# Keypad.net
KiCad netlist of a schematic drawn in EAGLE
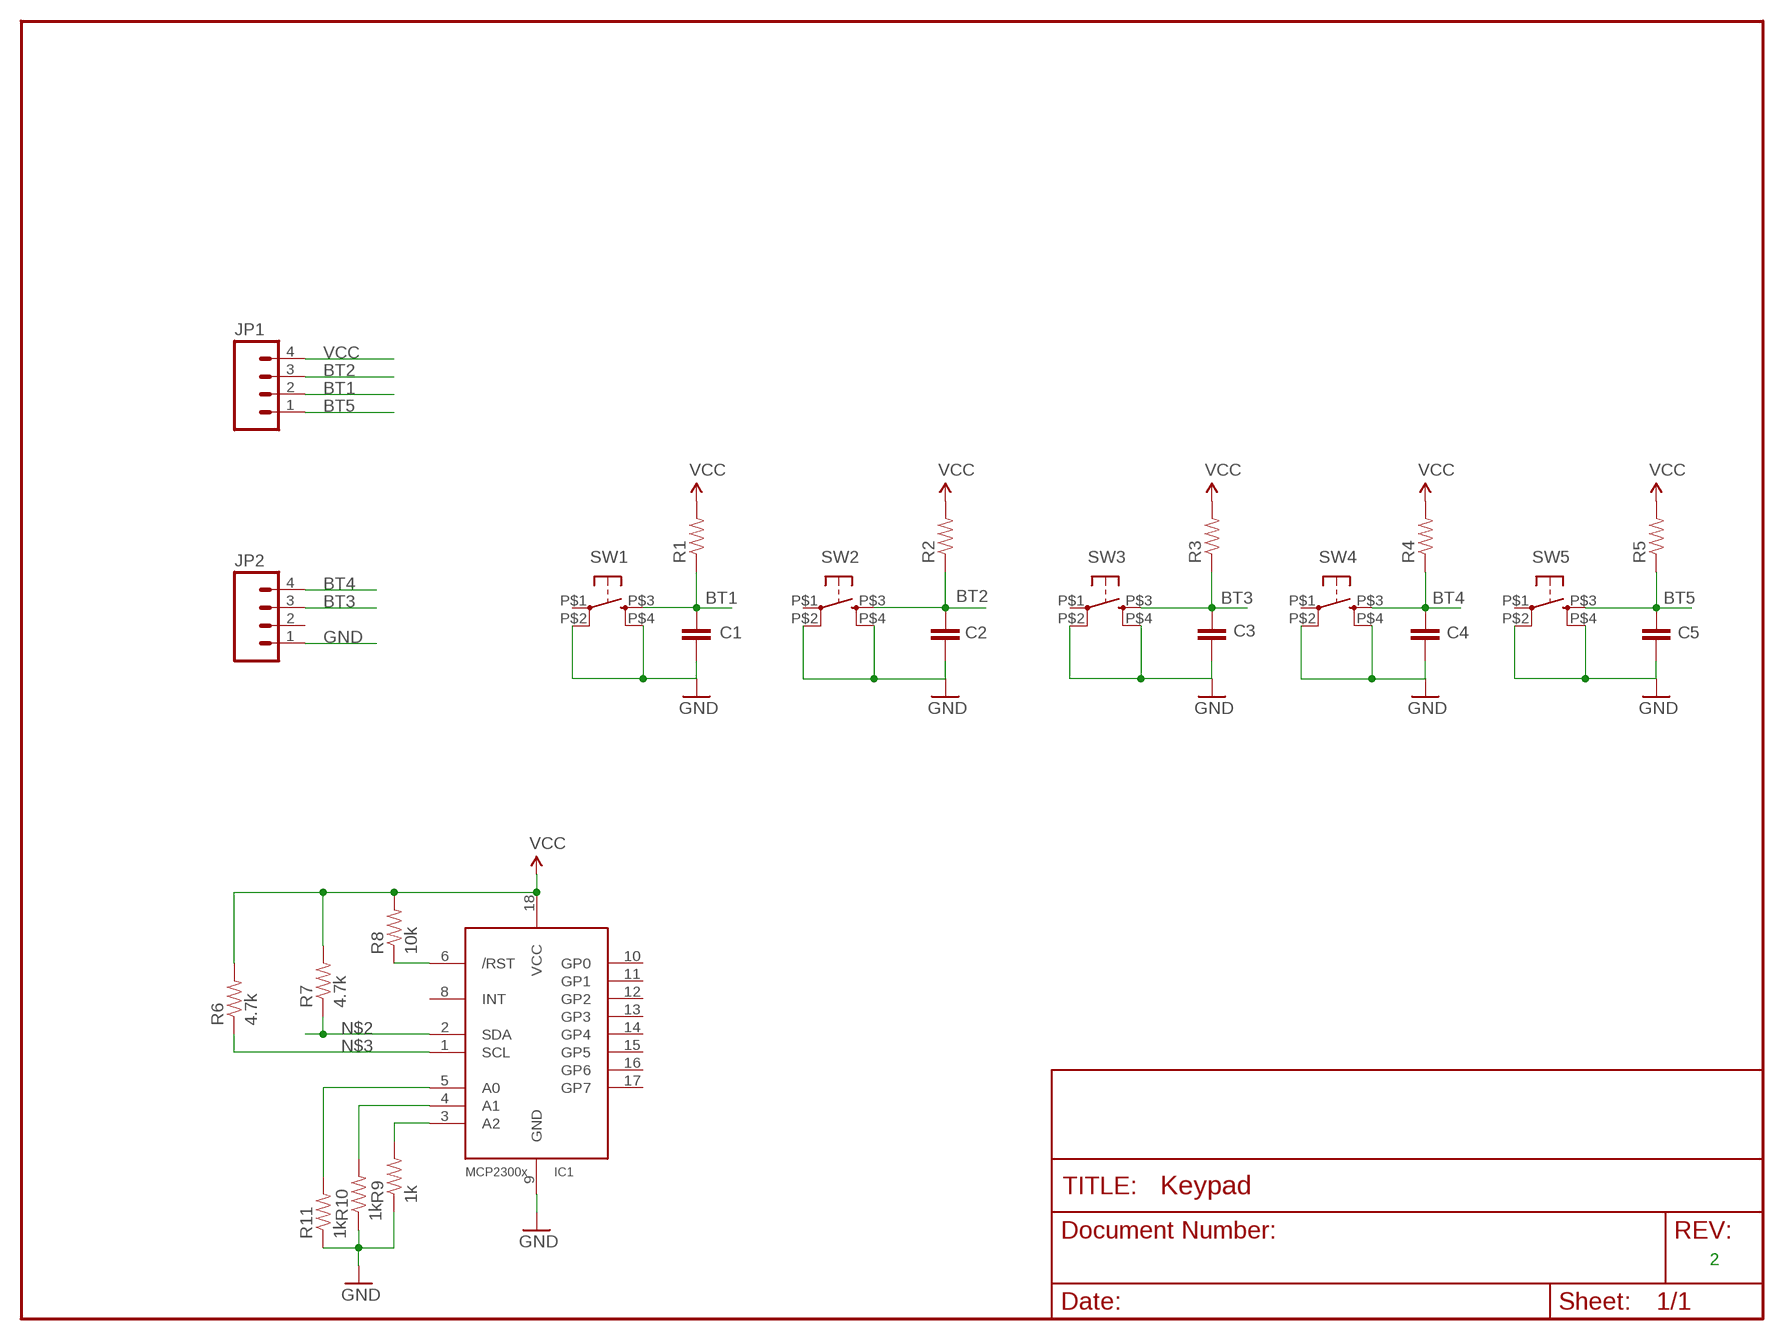
[diagram p0: schematic, sheet 1]

(export (version "E")
  (design (tool "Eeschema 10.0.6"))
  (components
    (comp (ref "C1")
      (value "CAP1206")
      (footprint "eagle-import:1206")
      (libsource (lib "eagle-import") (part "CAP1206"))
    )
    (comp (ref "C2")
      (value "CAP1206")
      (footprint "eagle-import:1206")
      (libsource (lib "eagle-import") (part "CAP1206"))
    )
    (comp (ref "C3")
      (value "CAP1206")
      (footprint "eagle-import:1206")
      (libsource (lib "eagle-import") (part "CAP1206"))
    )
    (comp (ref "C4")
      (value "CAP1206")
      (footprint "eagle-import:1206")
      (libsource (lib "eagle-import") (part "CAP1206"))
    )
    (comp (ref "C5")
      (value "CAP1206")
      (footprint "eagle-import:1206")
      (libsource (lib "eagle-import") (part "CAP1206"))
    )
    (comp (ref "IC1")
      (value "MCP2300X/SO")
      (footprint "eagle-import:SO18W")
      (libsource (lib "eagle-import") (part "MCP2300X/SO"))
    )
    (comp (ref "JP1")
      (value "M04LOCK")
      (footprint "eagle-import:1X04_LOCK")
      (libsource (lib "eagle-import") (part "M04LOCK"))
    )
    (comp (ref "JP2")
      (value "M04LOCK")
      (footprint "eagle-import:1X04_LOCK")
      (libsource (lib "eagle-import") (part "M04LOCK"))
    )
    (comp (ref "R1")
      (value "RESISTOR1206")
      (footprint "eagle-import:1206")
      (libsource (lib "eagle-import") (part "RESISTOR1206"))
    )
    (comp (ref "R2")
      (value "RESISTOR1206")
      (footprint "eagle-import:1206")
      (libsource (lib "eagle-import") (part "RESISTOR1206"))
    )
    (comp (ref "R3")
      (value "RESISTOR1206")
      (footprint "eagle-import:1206")
      (libsource (lib "eagle-import") (part "RESISTOR1206"))
    )
    (comp (ref "R4")
      (value "RESISTOR1206")
      (footprint "eagle-import:1206")
      (libsource (lib "eagle-import") (part "RESISTOR1206"))
    )
    (comp (ref "R5")
      (value "RESISTOR1206")
      (footprint "eagle-import:1206")
      (libsource (lib "eagle-import") (part "RESISTOR1206"))
    )
    (comp (ref "R6")
      (value "4.7k")
      (footprint "eagle-import:1206")
      (libsource (lib "eagle-import") (part "RESISTOR1206"))
    )
    (comp (ref "R7")
      (value "4.7k")
      (footprint "eagle-import:1206")
      (libsource (lib "eagle-import") (part "RESISTOR1206"))
    )
    (comp (ref "R8")
      (value "10k")
      (footprint "eagle-import:1206")
      (libsource (lib "eagle-import") (part "RESISTOR1206"))
    )
    (comp (ref "R9")
      (value "1k")
      (footprint "eagle-import:1206")
      (libsource (lib "eagle-import") (part "RESISTOR1206"))
    )
    (comp (ref "R10")
      (value "1k")
      (footprint "eagle-import:1206")
      (libsource (lib "eagle-import") (part "RESISTOR1206"))
    )
    (comp (ref "R11")
      (value "1k")
      (footprint "eagle-import:1206")
      (libsource (lib "eagle-import") (part "RESISTOR1206"))
    )
    (comp (ref "SW1")
      (value "TAC_PTH_12MM")
      (footprint "eagle-import:TACTILE-PTH-12MM")
      (libsource (lib "eagle-import") (part "TAC_PTH_12MM"))
    )
    (comp (ref "SW2")
      (value "TAC_PTH_12MM")
      (footprint "eagle-import:TACTILE-PTH-12MM")
      (libsource (lib "eagle-import") (part "TAC_PTH_12MM"))
    )
    (comp (ref "SW3")
      (value "TAC_PTH_12MM")
      (footprint "eagle-import:TACTILE-PTH-12MM")
      (libsource (lib "eagle-import") (part "TAC_PTH_12MM"))
    )
    (comp (ref "SW4")
      (value "TAC_PTH_12MM")
      (footprint "eagle-import:TACTILE-PTH-12MM")
      (libsource (lib "eagle-import") (part "TAC_PTH_12MM"))
    )
    (comp (ref "SW5")
      (value "TAC_PTH_12MM")
      (footprint "eagle-import:TACTILE-PTH-12MM")
      (libsource (lib "eagle-import") (part "TAC_PTH_12MM"))
    )
  )
  (nets
    (net (code "1") (name "/BT1") (class "Default")
      (node (ref "C1") (pin "1") (pinfunction "1_1") (pintype "passive"))
      (node (ref "JP1") (pin "2") (pinfunction "2_2") (pintype "passive"))
      (node (ref "R1") (pin "1") (pinfunction "1_1") (pintype "passive"))
      (node (ref "SW1") (pin "P$3") (pinfunction "3_P$3") (pintype "passive"))
    )
    (net (code "2") (name "/BT2") (class "Default")
      (node (ref "C2") (pin "1") (pinfunction "1_1") (pintype "passive"))
      (node (ref "JP1") (pin "3") (pinfunction "3_3") (pintype "passive"))
      (node (ref "R2") (pin "1") (pinfunction "1_1") (pintype "passive"))
      (node (ref "SW2") (pin "P$3") (pinfunction "3_P$3") (pintype "passive"))
    )
    (net (code "3") (name "/BT3") (class "Default")
      (node (ref "C3") (pin "1") (pinfunction "1_1") (pintype "passive"))
      (node (ref "JP2") (pin "3") (pinfunction "3_3") (pintype "passive"))
      (node (ref "R3") (pin "1") (pinfunction "1_1") (pintype "passive"))
      (node (ref "SW3") (pin "P$3") (pinfunction "3_P$3") (pintype "passive"))
    )
    (net (code "4") (name "/BT4") (class "Default")
      (node (ref "C4") (pin "1") (pinfunction "1_1") (pintype "passive"))
      (node (ref "JP2") (pin "4") (pinfunction "4_4") (pintype "passive"))
      (node (ref "R4") (pin "1") (pinfunction "1_1") (pintype "passive"))
      (node (ref "SW4") (pin "P$3") (pinfunction "3_P$3") (pintype "passive"))
    )
    (net (code "5") (name "/BT5") (class "Default")
      (node (ref "C5") (pin "1") (pinfunction "1_1") (pintype "passive"))
      (node (ref "JP1") (pin "1") (pinfunction "1_1") (pintype "passive"))
      (node (ref "R5") (pin "1") (pinfunction "1_1") (pintype "passive"))
      (node (ref "SW5") (pin "P$3") (pinfunction "3_P$3") (pintype "passive"))
    )
    (net (code "6") (name "/N$2") (class "Default")
      (node (ref "IC1") (pin "2") (pinfunction "SDA_2") (pintype "bidirectional"))
      (node (ref "R7") (pin "1") (pinfunction "1_1") (pintype "passive"))
    )
    (net (code "7") (name "/N$3") (class "Default")
      (node (ref "IC1") (pin "1") (pinfunction "SCL_1") (pintype "bidirectional"))
      (node (ref "R6") (pin "1") (pinfunction "1_1") (pintype "passive"))
    )
    (net (code "8") (name "GND") (class "Default")
      (node (ref "C1") (pin "2") (pinfunction "2_2") (pintype "passive"))
      (node (ref "C2") (pin "2") (pinfunction "2_2") (pintype "passive"))
      (node (ref "C3") (pin "2") (pinfunction "2_2") (pintype "passive"))
      (node (ref "C4") (pin "2") (pinfunction "2_2") (pintype "passive"))
      (node (ref "C5") (pin "2") (pinfunction "2_2") (pintype "passive"))
      (node (ref "IC1") (pin "9") (pinfunction "GND_9") (pintype "power_in"))
      (node (ref "JP2") (pin "1") (pinfunction "1_1") (pintype "passive"))
      (node (ref "R10") (pin "1") (pinfunction "1_1") (pintype "passive"))
      (node (ref "R11") (pin "1") (pinfunction "1_1") (pintype "passive"))
      (node (ref "R9") (pin "1") (pinfunction "1_1") (pintype "passive"))
      (node (ref "SW1") (pin "P$2") (pinfunction "2_P$2") (pintype "passive"))
      (node (ref "SW1") (pin "P$4") (pinfunction "4_P$4") (pintype "passive"))
      (node (ref "SW2") (pin "P$2") (pinfunction "2_P$2") (pintype "passive"))
      (node (ref "SW2") (pin "P$4") (pinfunction "4_P$4") (pintype "passive"))
      (node (ref "SW3") (pin "P$2") (pinfunction "2_P$2") (pintype "passive"))
      (node (ref "SW3") (pin "P$4") (pinfunction "4_P$4") (pintype "passive"))
      (node (ref "SW4") (pin "P$2") (pinfunction "2_P$2") (pintype "passive"))
      (node (ref "SW4") (pin "P$4") (pinfunction "4_P$4") (pintype "passive"))
      (node (ref "SW5") (pin "P$2") (pinfunction "2_P$2") (pintype "passive"))
      (node (ref "SW5") (pin "P$4") (pinfunction "4_P$4") (pintype "passive"))
    )
    (net (code "9") (name "Net-(IC1-A0)") (class "Default")
      (node (ref "IC1") (pin "5") (pinfunction "A0_5") (pintype "input"))
      (node (ref "R11") (pin "2") (pinfunction "2_2") (pintype "passive"))
    )
    (net (code "10") (name "Net-(IC1-A1)") (class "Default")
      (node (ref "IC1") (pin "4") (pinfunction "A1_4") (pintype "input"))
      (node (ref "R10") (pin "2") (pinfunction "2_2") (pintype "passive"))
    )
    (net (code "11") (name "Net-(IC1-A2)") (class "Default")
      (node (ref "IC1") (pin "3") (pinfunction "A2_3") (pintype "input"))
      (node (ref "R9") (pin "2") (pinfunction "2_2") (pintype "passive"))
    )
    (net (code "12") (name "Net-(IC1-{slash}RST)") (class "Default")
      (node (ref "IC1") (pin "6") (pinfunction "/RST_6") (pintype "input"))
      (node (ref "R8") (pin "1") (pinfunction "1_1") (pintype "passive"))
    )
    (net (code "13") (name "VCC") (class "Default")
      (node (ref "IC1") (pin "18") (pinfunction "VCC_18") (pintype "power_in"))
      (node (ref "JP1") (pin "4") (pinfunction "4_4") (pintype "passive"))
      (node (ref "R1") (pin "2") (pinfunction "2_2") (pintype "passive"))
      (node (ref "R2") (pin "2") (pinfunction "2_2") (pintype "passive"))
      (node (ref "R3") (pin "2") (pinfunction "2_2") (pintype "passive"))
      (node (ref "R4") (pin "2") (pinfunction "2_2") (pintype "passive"))
      (node (ref "R5") (pin "2") (pinfunction "2_2") (pintype "passive"))
      (node (ref "R6") (pin "2") (pinfunction "2_2") (pintype "passive"))
      (node (ref "R7") (pin "2") (pinfunction "2_2") (pintype "passive"))
      (node (ref "R8") (pin "2") (pinfunction "2_2") (pintype "passive"))
    )
    (net (code "14") (name "unconnected-(IC1-GP0-Pad10)") (class "Default")
      (node (ref "IC1") (pin "10") (pinfunction "GP0_10") (pintype "bidirectional"))
    )
    (net (code "15") (name "unconnected-(IC1-GP1-Pad11)") (class "Default")
      (node (ref "IC1") (pin "11") (pinfunction "GP1_11") (pintype "bidirectional"))
    )
    (net (code "16") (name "unconnected-(IC1-GP2-Pad12)") (class "Default")
      (node (ref "IC1") (pin "12") (pinfunction "GP2_12") (pintype "bidirectional"))
    )
    (net (code "17") (name "unconnected-(IC1-GP3-Pad13)") (class "Default")
      (node (ref "IC1") (pin "13") (pinfunction "GP3_13") (pintype "bidirectional"))
    )
    (net (code "18") (name "unconnected-(IC1-GP4-Pad14)") (class "Default")
      (node (ref "IC1") (pin "14") (pinfunction "GP4_14") (pintype "bidirectional"))
    )
    (net (code "19") (name "unconnected-(IC1-GP5-Pad15)") (class "Default")
      (node (ref "IC1") (pin "15") (pinfunction "GP5_15") (pintype "bidirectional"))
    )
    (net (code "20") (name "unconnected-(IC1-GP6-Pad16)") (class "Default")
      (node (ref "IC1") (pin "16") (pinfunction "GP6_16") (pintype "bidirectional"))
    )
    (net (code "21") (name "unconnected-(IC1-GP7-Pad17)") (class "Default")
      (node (ref "IC1") (pin "17") (pinfunction "GP7_17") (pintype "bidirectional"))
    )
    (net (code "22") (name "unconnected-(IC1-INT-Pad8)") (class "Default")
      (node (ref "IC1") (pin "8") (pinfunction "INT_8") (pintype "output"))
    )
    (net (code "23") (name "unconnected-(JP2-Pad2)") (class "Default")
      (node (ref "JP2") (pin "2") (pinfunction "2_2") (pintype "passive"))
    )
    (net (code "24") (name "unconnected-(SW1-1-PadP$1)") (class "Default")
      (node (ref "SW1") (pin "P$1") (pinfunction "1_P$1") (pintype "passive"))
    )
    (net (code "25") (name "unconnected-(SW2-1-PadP$1)") (class "Default")
      (node (ref "SW2") (pin "P$1") (pinfunction "1_P$1") (pintype "passive"))
    )
    (net (code "26") (name "unconnected-(SW3-1-PadP$1)") (class "Default")
      (node (ref "SW3") (pin "P$1") (pinfunction "1_P$1") (pintype "passive"))
    )
    (net (code "27") (name "unconnected-(SW4-1-PadP$1)") (class "Default")
      (node (ref "SW4") (pin "P$1") (pinfunction "1_P$1") (pintype "passive"))
    )
    (net (code "28") (name "unconnected-(SW5-1-PadP$1)") (class "Default")
      (node (ref "SW5") (pin "P$1") (pinfunction "1_P$1") (pintype "passive"))
    )
  )
)
